# Clock1.net
KiCad netlist of a schematic drawn in EAGLE
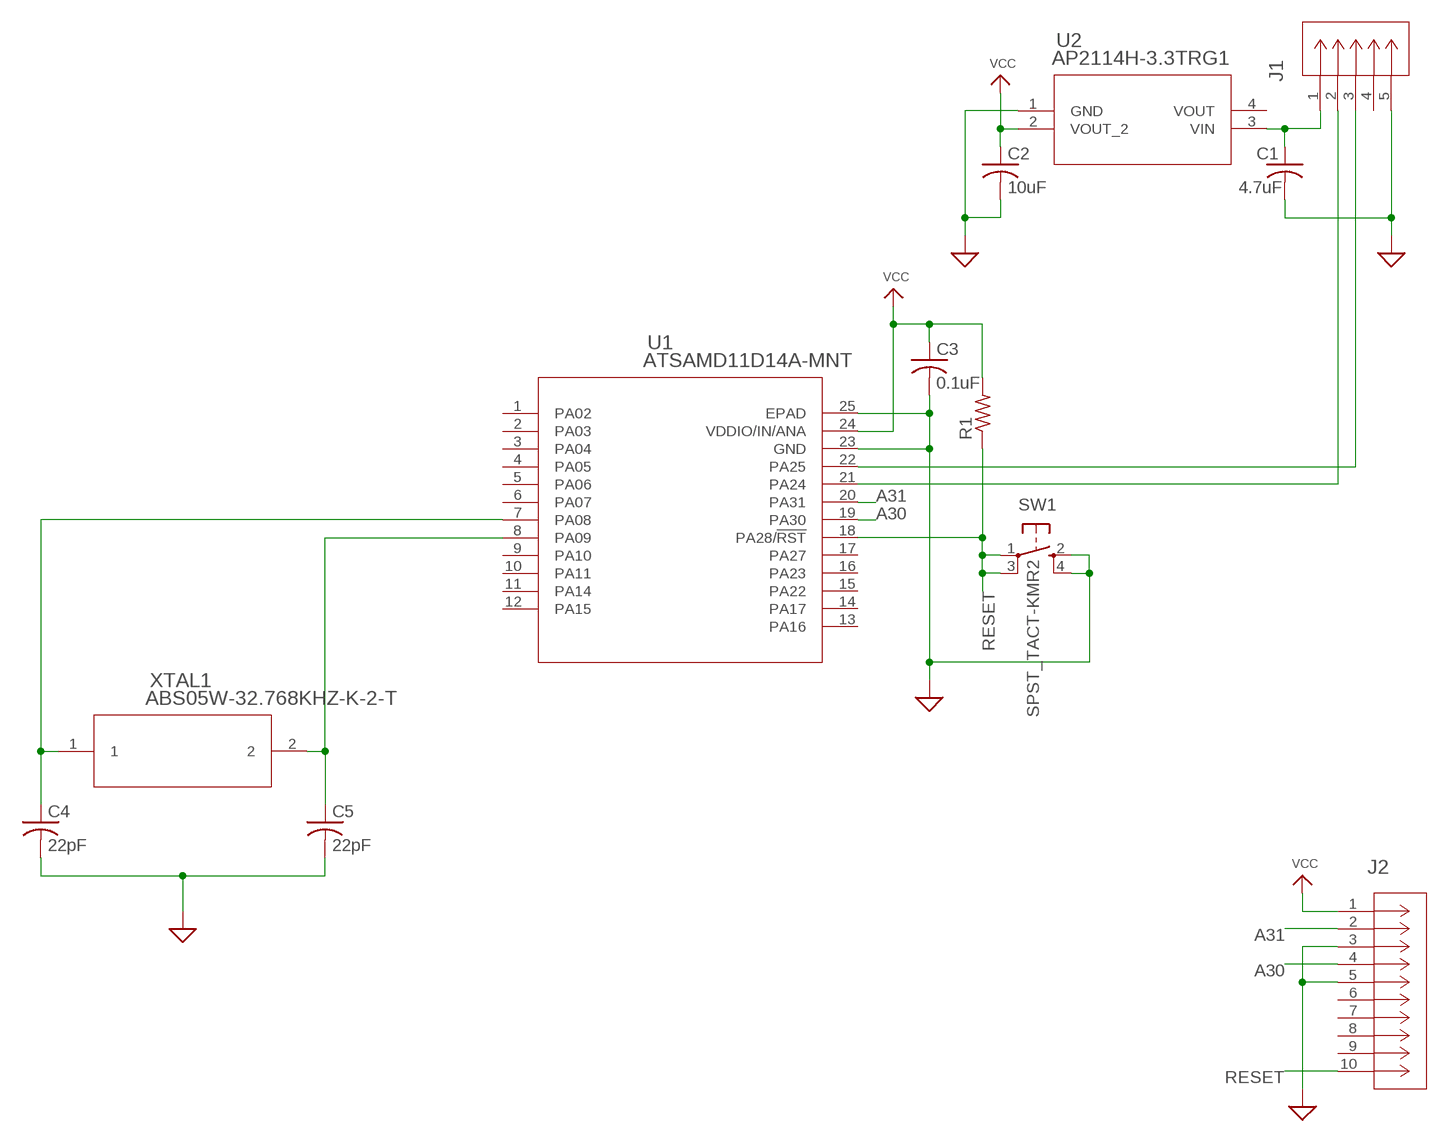
[diagram p0: schematic, sheet 1, part 1 of 2]
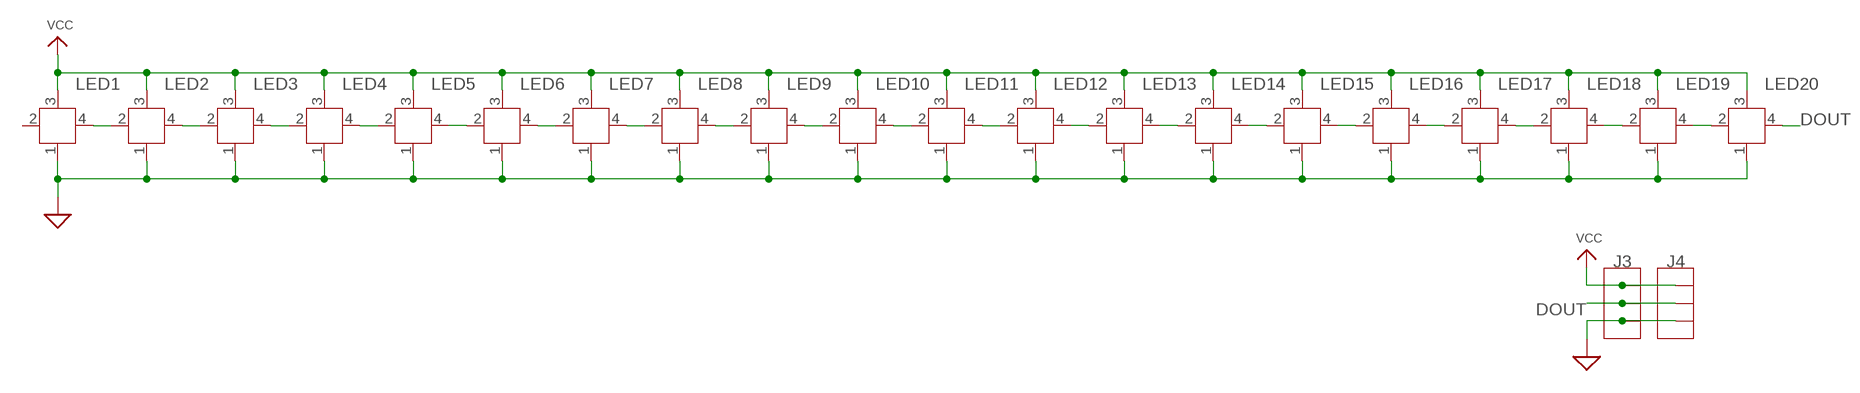
[diagram p1: schematic, sheet 1, part 2 of 2]

(export (version "E")
  (design (tool "Eeschema 10.0.6"))
  (components
    (comp (ref "C1")
      (value "4.7uF")
      (footprint "eagle-import:C0805")
      (libsource (lib "eagle-import") (part "C-USC0805"))
    )
    (comp (ref "C2")
      (value "10uF")
      (footprint "eagle-import:C0805")
      (libsource (lib "eagle-import") (part "C-USC0805"))
    )
    (comp (ref "C3")
      (value "0.1uF")
      (footprint "eagle-import:C0402")
      (libsource (lib "eagle-import") (part "C-USC0402"))
    )
    (comp (ref "C4")
      (value "22pF")
      (footprint "eagle-import:C0402")
      (libsource (lib "eagle-import") (part "C-USC0402"))
    )
    (comp (ref "C5")
      (value "22pF")
      (footprint "eagle-import:C0402")
      (libsource (lib "eagle-import") (part "C-USC0402"))
    )
    (comp (ref "J1")
      (value "1050171001")
      (footprint "eagle-import:CON00679_5")
      (fields (field (name "COPYRIGHT") "Copyright (C) 2016 Accelerated Designs. All rights reserved"))
      (libsource (lib "eagle-import") (part "1050171001"))
    )
    (comp (ref "J2")
      (value "20021121-00010C4LF")
      (footprint "eagle-import:CONN_00010C4LF")
      (fields (field (name "COPYRIGHT") "Copyright (C) 2018 Accelerated Designs. All rights reserved"))
      (libsource (lib "eagle-import") (part "20021121-00010C4LF"))
    )
    (comp (ref "J3")
      (value "HEADER_1X3FEMALE")
      (footprint "eagle-import:F3SMD")
      (libsource (lib "eagle-import") (part "HEADER_1X3FEMALE"))
    )
    (comp (ref "J4")
      (value "HEADER_1X3FEMALE")
      (footprint "eagle-import:F3SMD")
      (libsource (lib "eagle-import") (part "HEADER_1X3FEMALE"))
    )
    (comp (ref "LED1")
      (value "WS2812B")
      (footprint "eagle-import:SK6812")
      (libsource (lib "eagle-import") (part "WS2812B"))
    )
    (comp (ref "LED2")
      (value "WS2812B")
      (footprint "eagle-import:SK6812")
      (libsource (lib "eagle-import") (part "WS2812B"))
    )
    (comp (ref "LED3")
      (value "WS2812B")
      (footprint "eagle-import:SK6812")
      (libsource (lib "eagle-import") (part "WS2812B"))
    )
    (comp (ref "LED4")
      (value "WS2812B")
      (footprint "eagle-import:SK6812")
      (libsource (lib "eagle-import") (part "WS2812B"))
    )
    (comp (ref "LED5")
      (value "WS2812B")
      (footprint "eagle-import:SK6812")
      (libsource (lib "eagle-import") (part "WS2812B"))
    )
    (comp (ref "LED6")
      (value "WS2812B")
      (footprint "eagle-import:SK6812")
      (libsource (lib "eagle-import") (part "WS2812B"))
    )
    (comp (ref "LED7")
      (value "WS2812B")
      (footprint "eagle-import:SK6812")
      (libsource (lib "eagle-import") (part "WS2812B"))
    )
    (comp (ref "LED8")
      (value "WS2812B")
      (footprint "eagle-import:SK6812")
      (libsource (lib "eagle-import") (part "WS2812B"))
    )
    (comp (ref "LED9")
      (value "WS2812B")
      (footprint "eagle-import:SK6812")
      (libsource (lib "eagle-import") (part "WS2812B"))
    )
    (comp (ref "LED10")
      (value "WS2812B")
      (footprint "eagle-import:SK6812")
      (libsource (lib "eagle-import") (part "WS2812B"))
    )
    (comp (ref "LED11")
      (value "WS2812B")
      (footprint "eagle-import:SK6812")
      (libsource (lib "eagle-import") (part "WS2812B"))
    )
    (comp (ref "LED12")
      (value "WS2812B")
      (footprint "eagle-import:SK6812")
      (libsource (lib "eagle-import") (part "WS2812B"))
    )
    (comp (ref "LED13")
      (value "WS2812B")
      (footprint "eagle-import:SK6812")
      (libsource (lib "eagle-import") (part "WS2812B"))
    )
    (comp (ref "LED14")
      (value "WS2812B")
      (footprint "eagle-import:SK6812")
      (libsource (lib "eagle-import") (part "WS2812B"))
    )
    (comp (ref "LED15")
      (value "WS2812B")
      (footprint "eagle-import:SK6812")
      (libsource (lib "eagle-import") (part "WS2812B"))
    )
    (comp (ref "LED16")
      (value "WS2812B")
      (footprint "eagle-import:SK6812")
      (libsource (lib "eagle-import") (part "WS2812B"))
    )
    (comp (ref "LED17")
      (value "WS2812B")
      (footprint "eagle-import:SK6812")
      (libsource (lib "eagle-import") (part "WS2812B"))
    )
    (comp (ref "LED18")
      (value "WS2812B")
      (footprint "eagle-import:SK6812")
      (libsource (lib "eagle-import") (part "WS2812B"))
    )
    (comp (ref "LED19")
      (value "WS2812B")
      (footprint "eagle-import:SK6812")
      (libsource (lib "eagle-import") (part "WS2812B"))
    )
    (comp (ref "LED20")
      (value "WS2812B")
      (footprint "eagle-import:SK6812")
      (libsource (lib "eagle-import") (part "WS2812B"))
    )
    (comp (ref "R1")
      (value "R-US_R0402")
      (footprint "eagle-import:R0402")
      (libsource (lib "eagle-import") (part "R-US_R0402"))
    )
    (comp (ref "SW1")
      (value "SPST_TACT-KMR2")
      (footprint "eagle-import:KMR2")
      (libsource (lib "eagle-import") (part "SPST_TACT-KMR2"))
    )
    (comp (ref "U1")
      (value "ATSAMD11D14A-MNT")
      (footprint "eagle-import:QFN24_4X4MC")
      (fields (field (name "COPYRIGHT") "Copyright (C) 2018 Accelerated Designs. All rights reserved"))
      (libsource (lib "eagle-import") (part "ATSAMD11D14A-MNT"))
    )
    (comp (ref "U2")
      (value "AP2114H-3.3TRG1")
      (footprint "eagle-import:SOT-223")
      (libsource (lib "eagle-import") (part "AP2114H-3.3TRG1"))
    )
    (comp (ref "XTAL1")
      (value "ABS05W-32.768KHZ-K-2-T")
      (footprint "eagle-import:XTAL_ABS05")
      (fields (field (name "COPYRIGHT") "Copyright (C) 2018 Accelerated Designs. All rights reserved"))
      (libsource (lib "eagle-import") (part "ABS05W-32.768KHZ-K-2-T"))
    )
  )
  (nets
    (net (code "1") (name "/A30") (class "Default")
      (node (ref "J2") (pin "4") (pinfunction "4_4") (pintype "passive"))
      (node (ref "U1") (pin "19") (pinfunction "PA30_19") (pintype "bidirectional"))
    )
    (net (code "2") (name "/A31") (class "Default")
      (node (ref "J2") (pin "2") (pinfunction "2_2") (pintype "passive"))
      (node (ref "U1") (pin "20") (pinfunction "PA31_20") (pintype "bidirectional"))
    )
    (net (code "3") (name "/DOUT") (class "Default")
      (node (ref "J3") (pin "2A") (pinfunction "P$2_2A") (pintype "bidirectional"))
      (node (ref "J3") (pin "2B") (pinfunction "P$2_2B") (pintype "bidirectional"))
      (node (ref "J4") (pin "2A") (pinfunction "P$2_2A") (pintype "bidirectional"))
      (node (ref "J4") (pin "2B") (pinfunction "P$2_2B") (pintype "bidirectional"))
      (node (ref "LED20") (pin "4") (pinfunction "DOUT_4") (pintype "bidirectional"))
    )
    (net (code "4") (name "/RESET") (class "Default")
      (node (ref "J2") (pin "10") (pinfunction "10_10") (pintype "passive"))
      (node (ref "R1") (pin "1") (pinfunction "1_1") (pintype "passive"))
      (node (ref "SW1") (pin "1") (pinfunction "P_1") (pintype "passive"))
      (node (ref "SW1") (pin "3") (pinfunction "P1_3") (pintype "passive"))
      (node (ref "U1") (pin "18") (pinfunction "PA28/~{RST}_18") (pintype "bidirectional"))
    )
    (net (code "5") (name "Net-(LED1-DOUT)") (class "Default")
      (node (ref "LED1") (pin "4") (pinfunction "DOUT_4") (pintype "bidirectional"))
      (node (ref "LED2") (pin "2") (pinfunction "DIN_2") (pintype "bidirectional"))
    )
    (net (code "6") (name "Net-(LED2-DOUT)") (class "Default")
      (node (ref "LED2") (pin "4") (pinfunction "DOUT_4") (pintype "bidirectional"))
      (node (ref "LED3") (pin "2") (pinfunction "DIN_2") (pintype "bidirectional"))
    )
    (net (code "7") (name "Net-(LED3-DOUT)") (class "Default")
      (node (ref "LED3") (pin "4") (pinfunction "DOUT_4") (pintype "bidirectional"))
      (node (ref "LED4") (pin "2") (pinfunction "DIN_2") (pintype "bidirectional"))
    )
    (net (code "8") (name "Net-(LED4-DOUT)") (class "Default")
      (node (ref "LED4") (pin "4") (pinfunction "DOUT_4") (pintype "bidirectional"))
      (node (ref "LED5") (pin "2") (pinfunction "DIN_2") (pintype "bidirectional"))
    )
    (net (code "9") (name "Net-(LED5-DOUT)") (class "Default")
      (node (ref "LED5") (pin "4") (pinfunction "DOUT_4") (pintype "bidirectional"))
      (node (ref "LED6") (pin "2") (pinfunction "DIN_2") (pintype "bidirectional"))
    )
    (net (code "10") (name "Net-(LED6-DOUT)") (class "Default")
      (node (ref "LED6") (pin "4") (pinfunction "DOUT_4") (pintype "bidirectional"))
      (node (ref "LED7") (pin "2") (pinfunction "DIN_2") (pintype "bidirectional"))
    )
    (net (code "11") (name "Net-(LED7-DOUT)") (class "Default")
      (node (ref "LED7") (pin "4") (pinfunction "DOUT_4") (pintype "bidirectional"))
      (node (ref "LED8") (pin "2") (pinfunction "DIN_2") (pintype "bidirectional"))
    )
    (net (code "12") (name "Net-(LED8-DOUT)") (class "Default")
      (node (ref "LED8") (pin "4") (pinfunction "DOUT_4") (pintype "bidirectional"))
      (node (ref "LED9") (pin "2") (pinfunction "DIN_2") (pintype "bidirectional"))
    )
    (net (code "13") (name "Net-(LED10-DIN)") (class "Default")
      (node (ref "LED10") (pin "2") (pinfunction "DIN_2") (pintype "bidirectional"))
      (node (ref "LED9") (pin "4") (pinfunction "DOUT_4") (pintype "bidirectional"))
    )
    (net (code "14") (name "Net-(LED10-DOUT)") (class "Default")
      (node (ref "LED10") (pin "4") (pinfunction "DOUT_4") (pintype "bidirectional"))
      (node (ref "LED11") (pin "2") (pinfunction "DIN_2") (pintype "bidirectional"))
    )
    (net (code "15") (name "Net-(LED11-DOUT)") (class "Default")
      (node (ref "LED11") (pin "4") (pinfunction "DOUT_4") (pintype "bidirectional"))
      (node (ref "LED12") (pin "2") (pinfunction "DIN_2") (pintype "bidirectional"))
    )
    (net (code "16") (name "Net-(LED12-DOUT)") (class "Default")
      (node (ref "LED12") (pin "4") (pinfunction "DOUT_4") (pintype "bidirectional"))
      (node (ref "LED13") (pin "2") (pinfunction "DIN_2") (pintype "bidirectional"))
    )
    (net (code "17") (name "Net-(LED13-DOUT)") (class "Default")
      (node (ref "LED13") (pin "4") (pinfunction "DOUT_4") (pintype "bidirectional"))
      (node (ref "LED14") (pin "2") (pinfunction "DIN_2") (pintype "bidirectional"))
    )
    (net (code "18") (name "Net-(LED14-DOUT)") (class "Default")
      (node (ref "LED14") (pin "4") (pinfunction "DOUT_4") (pintype "bidirectional"))
      (node (ref "LED15") (pin "2") (pinfunction "DIN_2") (pintype "bidirectional"))
    )
    (net (code "19") (name "Net-(LED15-DOUT)") (class "Default")
      (node (ref "LED15") (pin "4") (pinfunction "DOUT_4") (pintype "bidirectional"))
      (node (ref "LED16") (pin "2") (pinfunction "DIN_2") (pintype "bidirectional"))
    )
    (net (code "20") (name "Net-(LED16-DOUT)") (class "Default")
      (node (ref "LED16") (pin "4") (pinfunction "DOUT_4") (pintype "bidirectional"))
      (node (ref "LED17") (pin "2") (pinfunction "DIN_2") (pintype "bidirectional"))
    )
    (net (code "21") (name "Net-(LED17-DOUT)") (class "Default")
      (node (ref "LED17") (pin "4") (pinfunction "DOUT_4") (pintype "bidirectional"))
      (node (ref "LED18") (pin "2") (pinfunction "DIN_2") (pintype "bidirectional"))
    )
    (net (code "22") (name "Net-(LED18-DOUT)") (class "Default")
      (node (ref "LED18") (pin "4") (pinfunction "DOUT_4") (pintype "bidirectional"))
      (node (ref "LED19") (pin "2") (pinfunction "DIN_2") (pintype "bidirectional"))
    )
    (net (code "23") (name "Net-(LED19-DOUT)") (class "Default")
      (node (ref "LED19") (pin "4") (pinfunction "DOUT_4") (pintype "bidirectional"))
      (node (ref "LED20") (pin "2") (pinfunction "DIN_2") (pintype "bidirectional"))
    )
    (net (code "24") (name "Net-(U1-PA08)") (class "Default")
      (node (ref "C4") (pin "1") (pinfunction "1_1") (pintype "passive"))
      (node (ref "U1") (pin "7") (pinfunction "PA08_7") (pintype "bidirectional"))
      (node (ref "XTAL1") (pin "1") (pinfunction "1_1") (pintype "passive"))
    )
    (net (code "25") (name "Net-(U1-PA09)") (class "Default")
      (node (ref "C5") (pin "1") (pinfunction "1_1") (pintype "passive"))
      (node (ref "U1") (pin "8") (pinfunction "PA09_8") (pintype "bidirectional"))
      (node (ref "XTAL1") (pin "2") (pinfunction "2_2") (pintype "passive"))
    )
    (net (code "26") (name "Net-(U1-PA24)") (class "Default")
      (node (ref "J1") (pin "2") (pinfunction "2_2") (pintype "passive"))
      (node (ref "U1") (pin "21") (pinfunction "PA24_21") (pintype "bidirectional"))
    )
    (net (code "27") (name "Net-(U1-PA25)") (class "Default")
      (node (ref "J1") (pin "3") (pinfunction "3_3") (pintype "passive"))
      (node (ref "U1") (pin "22") (pinfunction "PA25_22") (pintype "bidirectional"))
    )
    (net (code "28") (name "Net-(U2-VIN)") (class "Default")
      (node (ref "C1") (pin "1") (pinfunction "1_1") (pintype "passive"))
      (node (ref "J1") (pin "1") (pinfunction "1_1") (pintype "passive"))
      (node (ref "U2") (pin "3") (pinfunction "VIN_3") (pintype "input"))
    )
    (net (code "29") (name "SUP") (class "Default")
      (node (ref "C1") (pin "2") (pinfunction "2_2") (pintype "passive"))
      (node (ref "C2") (pin "2") (pinfunction "2_2") (pintype "passive"))
      (node (ref "C3") (pin "2") (pinfunction "2_2") (pintype "passive"))
      (node (ref "C4") (pin "2") (pinfunction "2_2") (pintype "passive"))
      (node (ref "C5") (pin "2") (pinfunction "2_2") (pintype "passive"))
      (node (ref "J1") (pin "5") (pinfunction "5_5") (pintype "passive"))
      (node (ref "J2") (pin "3") (pinfunction "3_3") (pintype "passive"))
      (node (ref "J2") (pin "5") (pinfunction "5_5") (pintype "passive"))
      (node (ref "J3") (pin "3A") (pinfunction "P$3_3A") (pintype "bidirectional"))
      (node (ref "J3") (pin "3B") (pinfunction "P$3_3B") (pintype "bidirectional"))
      (node (ref "J4") (pin "3A") (pinfunction "P$3_3A") (pintype "bidirectional"))
      (node (ref "J4") (pin "3B") (pinfunction "P$3_3B") (pintype "bidirectional"))
      (node (ref "LED1") (pin "1") (pinfunction "VSS_1") (pintype "bidirectional"))
      (node (ref "LED10") (pin "1") (pinfunction "VSS_1") (pintype "bidirectional"))
      (node (ref "LED11") (pin "1") (pinfunction "VSS_1") (pintype "bidirectional"))
      (node (ref "LED12") (pin "1") (pinfunction "VSS_1") (pintype "bidirectional"))
      (node (ref "LED13") (pin "1") (pinfunction "VSS_1") (pintype "bidirectional"))
      (node (ref "LED14") (pin "1") (pinfunction "VSS_1") (pintype "bidirectional"))
      (node (ref "LED15") (pin "1") (pinfunction "VSS_1") (pintype "bidirectional"))
      (node (ref "LED16") (pin "1") (pinfunction "VSS_1") (pintype "bidirectional"))
      (node (ref "LED17") (pin "1") (pinfunction "VSS_1") (pintype "bidirectional"))
      (node (ref "LED18") (pin "1") (pinfunction "VSS_1") (pintype "bidirectional"))
      (node (ref "LED19") (pin "1") (pinfunction "VSS_1") (pintype "bidirectional"))
      (node (ref "LED2") (pin "1") (pinfunction "VSS_1") (pintype "bidirectional"))
      (node (ref "LED20") (pin "1") (pinfunction "VSS_1") (pintype "bidirectional"))
      (node (ref "LED3") (pin "1") (pinfunction "VSS_1") (pintype "bidirectional"))
      (node (ref "LED4") (pin "1") (pinfunction "VSS_1") (pintype "bidirectional"))
      (node (ref "LED5") (pin "1") (pinfunction "VSS_1") (pintype "bidirectional"))
      (node (ref "LED6") (pin "1") (pinfunction "VSS_1") (pintype "bidirectional"))
      (node (ref "LED7") (pin "1") (pinfunction "VSS_1") (pintype "bidirectional"))
      (node (ref "LED8") (pin "1") (pinfunction "VSS_1") (pintype "bidirectional"))
      (node (ref "LED9") (pin "1") (pinfunction "VSS_1") (pintype "bidirectional"))
      (node (ref "SW1") (pin "2") (pinfunction "S_2") (pintype "passive"))
      (node (ref "SW1") (pin "4") (pinfunction "S1_4") (pintype "passive"))
      (node (ref "U1") (pin "23") (pinfunction "GND_23") (pintype "passive"))
      (node (ref "U1") (pin "25") (pinfunction "EPAD_25") (pintype "passive"))
      (node (ref "U2") (pin "1") (pinfunction "GND_1") (pintype "passive"))
    )
    (net (code "30") (name "VCC") (class "Default")
      (node (ref "C2") (pin "1") (pinfunction "1_1") (pintype "passive"))
      (node (ref "C3") (pin "1") (pinfunction "1_1") (pintype "passive"))
      (node (ref "J2") (pin "1") (pinfunction "1_1") (pintype "passive"))
      (node (ref "J3") (pin "1A") (pinfunction "P$1_1A") (pintype "bidirectional"))
      (node (ref "J3") (pin "1B") (pinfunction "P$1_1B") (pintype "bidirectional"))
      (node (ref "J4") (pin "1A") (pinfunction "P$1_1A") (pintype "bidirectional"))
      (node (ref "J4") (pin "1B") (pinfunction "P$1_1B") (pintype "bidirectional"))
      (node (ref "LED1") (pin "3") (pinfunction "VDD_3") (pintype "bidirectional"))
      (node (ref "LED10") (pin "3") (pinfunction "VDD_3") (pintype "bidirectional"))
      (node (ref "LED11") (pin "3") (pinfunction "VDD_3") (pintype "bidirectional"))
      (node (ref "LED12") (pin "3") (pinfunction "VDD_3") (pintype "bidirectional"))
      (node (ref "LED13") (pin "3") (pinfunction "VDD_3") (pintype "bidirectional"))
      (node (ref "LED14") (pin "3") (pinfunction "VDD_3") (pintype "bidirectional"))
      (node (ref "LED15") (pin "3") (pinfunction "VDD_3") (pintype "bidirectional"))
      (node (ref "LED16") (pin "3") (pinfunction "VDD_3") (pintype "bidirectional"))
      (node (ref "LED17") (pin "3") (pinfunction "VDD_3") (pintype "bidirectional"))
      (node (ref "LED18") (pin "3") (pinfunction "VDD_3") (pintype "bidirectional"))
      (node (ref "LED19") (pin "3") (pinfunction "VDD_3") (pintype "bidirectional"))
      (node (ref "LED2") (pin "3") (pinfunction "VDD_3") (pintype "bidirectional"))
      (node (ref "LED20") (pin "3") (pinfunction "VDD_3") (pintype "bidirectional"))
      (node (ref "LED3") (pin "3") (pinfunction "VDD_3") (pintype "bidirectional"))
      (node (ref "LED4") (pin "3") (pinfunction "VDD_3") (pintype "bidirectional"))
      (node (ref "LED5") (pin "3") (pinfunction "VDD_3") (pintype "bidirectional"))
      (node (ref "LED6") (pin "3") (pinfunction "VDD_3") (pintype "bidirectional"))
      (node (ref "LED7") (pin "3") (pinfunction "VDD_3") (pintype "bidirectional"))
      (node (ref "LED8") (pin "3") (pinfunction "VDD_3") (pintype "bidirectional"))
      (node (ref "LED9") (pin "3") (pinfunction "VDD_3") (pintype "bidirectional"))
      (node (ref "R1") (pin "2") (pinfunction "2_2") (pintype "passive"))
      (node (ref "U1") (pin "24") (pinfunction "VDDIO/IN/ANA_24") (pintype "power_in"))
      (node (ref "U2") (pin "2") (pinfunction "VOUT_2_2") (pintype "output"))
    )
    (net (code "31") (name "unconnected-(J1-Pad4)") (class "Default")
      (node (ref "J1") (pin "4") (pinfunction "4_4") (pintype "passive"))
    )
    (net (code "32") (name "unconnected-(J2-Pad6)") (class "Default")
      (node (ref "J2") (pin "6") (pinfunction "6_6") (pintype "passive"))
    )
    (net (code "33") (name "unconnected-(J2-Pad7)") (class "Default")
      (node (ref "J2") (pin "7") (pinfunction "7_7") (pintype "passive"))
    )
    (net (code "34") (name "unconnected-(J2-Pad8)") (class "Default")
      (node (ref "J2") (pin "8") (pinfunction "8_8") (pintype "passive"))
    )
    (net (code "35") (name "unconnected-(J2-Pad9)") (class "Default")
      (node (ref "J2") (pin "9") (pinfunction "9_9") (pintype "passive"))
    )
    (net (code "36") (name "unconnected-(LED1-DIN-Pad2)") (class "Default")
      (node (ref "LED1") (pin "2") (pinfunction "DIN_2") (pintype "bidirectional"))
    )
    (net (code "37") (name "unconnected-(U1-PA02-Pad1)") (class "Default")
      (node (ref "U1") (pin "1") (pinfunction "PA02_1") (pintype "bidirectional"))
    )
    (net (code "38") (name "unconnected-(U1-PA03-Pad2)") (class "Default")
      (node (ref "U1") (pin "2") (pinfunction "PA03_2") (pintype "bidirectional"))
    )
    (net (code "39") (name "unconnected-(U1-PA04-Pad3)") (class "Default")
      (node (ref "U1") (pin "3") (pinfunction "PA04_3") (pintype "bidirectional"))
    )
    (net (code "40") (name "unconnected-(U1-PA05-Pad4)") (class "Default")
      (node (ref "U1") (pin "4") (pinfunction "PA05_4") (pintype "bidirectional"))
    )
    (net (code "41") (name "unconnected-(U1-PA06-Pad5)") (class "Default")
      (node (ref "U1") (pin "5") (pinfunction "PA06_5") (pintype "bidirectional"))
    )
    (net (code "42") (name "unconnected-(U1-PA07-Pad6)") (class "Default")
      (node (ref "U1") (pin "6") (pinfunction "PA07_6") (pintype "bidirectional"))
    )
    (net (code "43") (name "unconnected-(U1-PA10-Pad9)") (class "Default")
      (node (ref "U1") (pin "9") (pinfunction "PA10_9") (pintype "bidirectional"))
    )
    (net (code "44") (name "unconnected-(U1-PA11-Pad10)") (class "Default")
      (node (ref "U1") (pin "10") (pinfunction "PA11_10") (pintype "bidirectional"))
    )
    (net (code "45") (name "unconnected-(U1-PA14-Pad11)") (class "Default")
      (node (ref "U1") (pin "11") (pinfunction "PA14_11") (pintype "bidirectional"))
    )
    (net (code "46") (name "unconnected-(U1-PA15-Pad12)") (class "Default")
      (node (ref "U1") (pin "12") (pinfunction "PA15_12") (pintype "bidirectional"))
    )
    (net (code "47") (name "unconnected-(U1-PA16-Pad13)") (class "Default")
      (node (ref "U1") (pin "13") (pinfunction "PA16_13") (pintype "bidirectional"))
    )
    (net (code "48") (name "unconnected-(U1-PA17-Pad14)") (class "Default")
      (node (ref "U1") (pin "14") (pinfunction "PA17_14") (pintype "bidirectional"))
    )
    (net (code "49") (name "unconnected-(U1-PA22-Pad15)") (class "Default")
      (node (ref "U1") (pin "15") (pinfunction "PA22_15") (pintype "bidirectional"))
    )
    (net (code "50") (name "unconnected-(U1-PA23-Pad16)") (class "Default")
      (node (ref "U1") (pin "16") (pinfunction "PA23_16") (pintype "bidirectional"))
    )
    (net (code "51") (name "unconnected-(U1-PA27-Pad17)") (class "Default")
      (node (ref "U1") (pin "17") (pinfunction "PA27_17") (pintype "bidirectional"))
    )
    (net (code "52") (name "unconnected-(U2-VOUT-Pad4)") (class "Default")
      (node (ref "U2") (pin "4") (pinfunction "VOUT_4") (pintype "output"))
    )
  )
)
